# DRV__2024-10-17.net
KiCad netlist of a schematic drawn in EasyEDA Pro
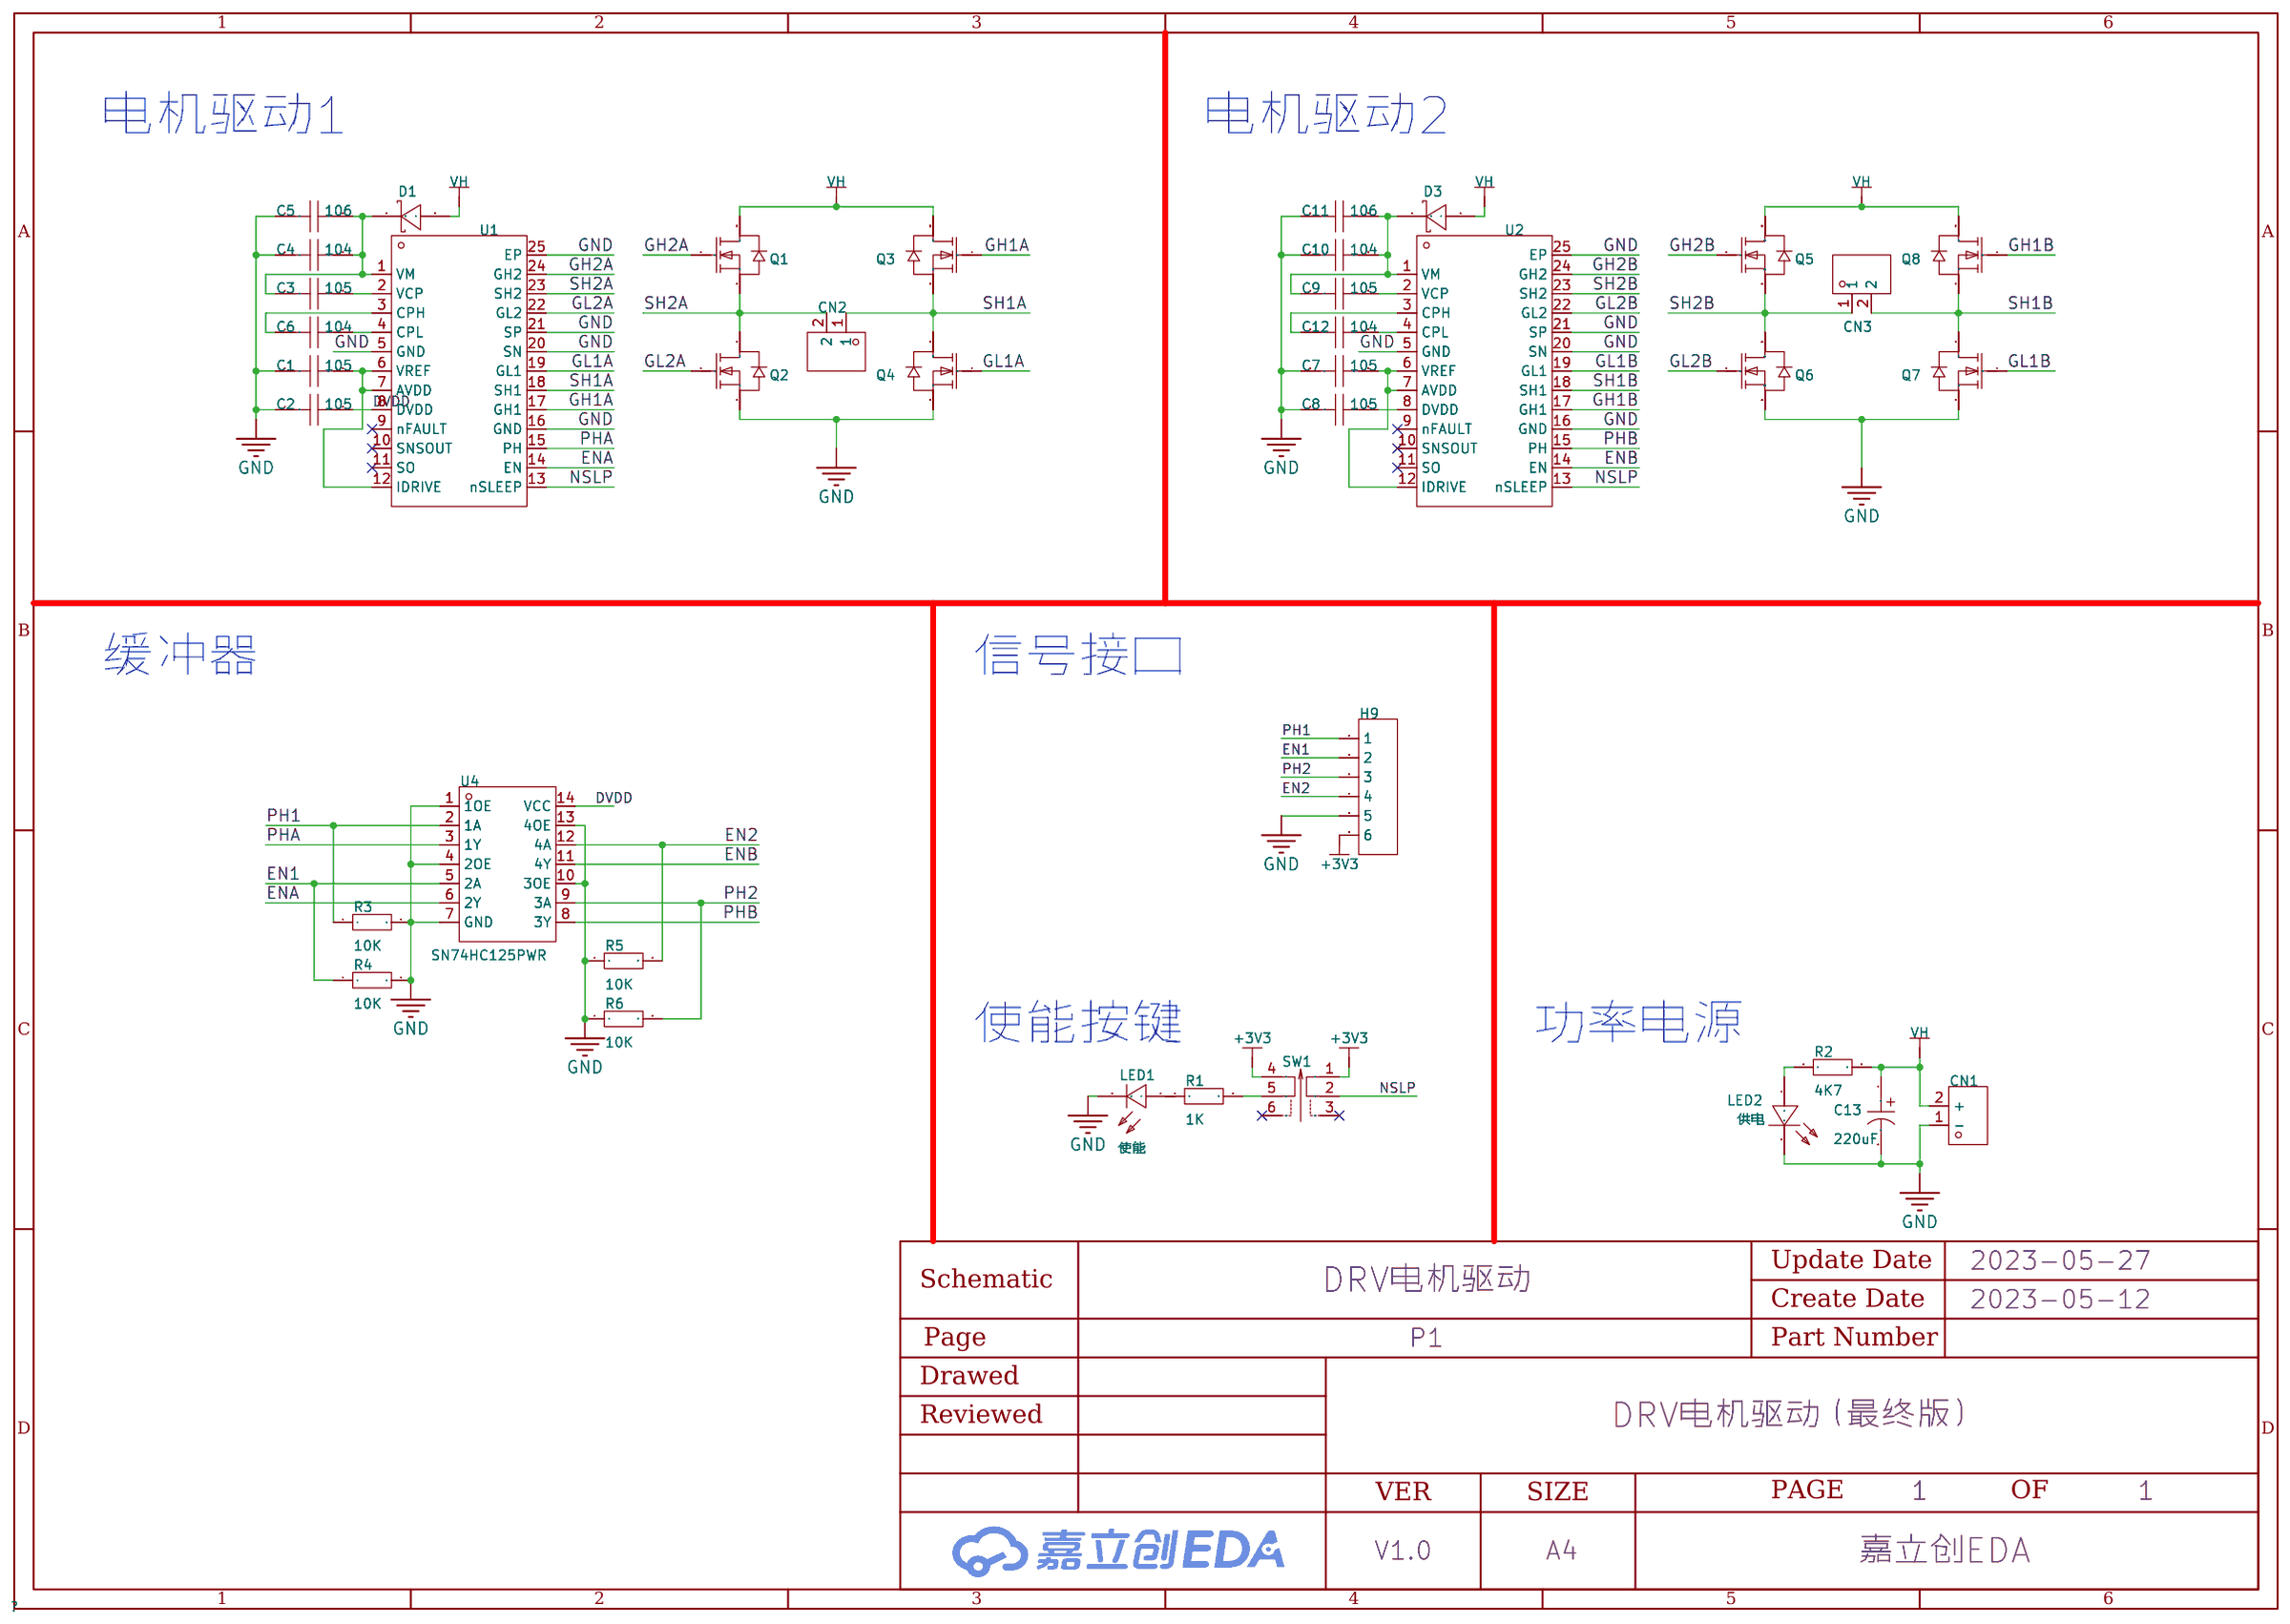
[diagram p0: schematic sheet]

(export (version "E")
  (design (tool "Eeschema 10.0.6"))
  (components
    (comp (ref "C1")
      (value "105")
      (footprint "easyedapro:C0603")
      (description "容值:100nF;精度:±10%;额定电压:50V;温度系数:X7R;")
      (libsource (lib "easyedapro") (part "C1210X7R475K630NT"))
    )
    (comp (ref "C2")
      (value "105")
      (footprint "easyedapro:C0603")
      (description "容值:100nF;精度:±10%;额定电压:50V;温度系数:X7R;")
      (libsource (lib "easyedapro") (part "C1210X7R475K630NT"))
    )
    (comp (ref "C3")
      (value "105")
      (footprint "easyedapro:C0603")
      (description "容值:100nF;精度:±10%;额定电压:50V;温度系数:X7R;")
      (libsource (lib "easyedapro") (part "C1210X7R475K630NT"))
    )
    (comp (ref "C4")
      (value "104")
      (footprint "easyedapro:C0603")
      (description "容值:100nF;精度:±10%;额定电压:50V;温度系数:X7R;")
      (libsource (lib "easyedapro") (part "C1210X7R475K630NT"))
    )
    (comp (ref "C5")
      (value "106")
      (footprint "easyedapro:C0603")
      (description "容值:100nF;精度:±10%;额定电压:50V;温度系数:X7R;")
      (libsource (lib "easyedapro") (part "C1210X7R475K630NT"))
    )
    (comp (ref "C6")
      (value "104")
      (footprint "easyedapro:C0603")
      (description "容值:100nF;精度:±10%;额定电压:50V;温度系数:X7R;")
      (libsource (lib "easyedapro") (part "C1210X7R475K630NT"))
    )
    (comp (ref "C7")
      (value "105")
      (footprint "easyedapro:C0603")
      (description "容值:100nF;精度:±10%;额定电压:50V;温度系数:X7R;")
      (libsource (lib "easyedapro") (part "C1210X7R475K630NT"))
    )
    (comp (ref "C8")
      (value "105")
      (footprint "easyedapro:C0603")
      (description "容值:100nF;精度:±10%;额定电压:50V;温度系数:X7R;")
      (libsource (lib "easyedapro") (part "C1210X7R475K630NT"))
    )
    (comp (ref "C9")
      (value "105")
      (footprint "easyedapro:C0603")
      (description "容值:100nF;精度:±10%;额定电压:50V;温度系数:X7R;")
      (libsource (lib "easyedapro") (part "C1210X7R475K630NT"))
    )
    (comp (ref "C10")
      (value "104")
      (footprint "easyedapro:C0603")
      (description "容值:100nF;精度:±10%;额定电压:50V;温度系数:X7R;")
      (libsource (lib "easyedapro") (part "C1210X7R475K630NT"))
    )
    (comp (ref "C11")
      (value "106")
      (footprint "easyedapro:C0603")
      (description "容值:100nF;精度:±10%;额定电压:50V;温度系数:X7R;")
      (libsource (lib "easyedapro") (part "C1210X7R475K630NT"))
    )
    (comp (ref "C12")
      (value "104")
      (footprint "easyedapro:C0603")
      (description "容值:100nF;精度:±10%;额定电压:50V;温度系数:X7R;")
      (libsource (lib "easyedapro") (part "C1210X7R475K630NT"))
    )
    (comp (ref "C13")
      (value "220uF")
      (footprint "easyedapro:CAP-TH_BD8.0-P3.50-D0.6-FD")
      (description "类型:-;容值:220uF;精度:±20%;额定电压:25V;电容体直径:-;电容体长度:-;脚间距:-;纹波电流:-;等效串联电阻:-;工作寿命:-;工作温度:-;")
      (fields (field (name "Manufacturer Part") "250ARHA221M08A2") (field (name "Manufacturer") "APAQ(钰邦)"))
      (libsource (lib "easyedapro") (part "250ARHA221M08A2"))
    )
    (comp (ref "CN1")
      (value "~")
      (footprint "easyedapro:CONN-TH_XT30UPB-M")
      (fields (field (name "Manufacturer Part") "XT30UPB-M") (field (name "Manufacturer") "AMASS(艾迈斯)"))
      (libsource (lib "easyedapro") (part "XT30UPB-M"))
    )
    (comp (ref "CN2")
      (value "KF301-5.0-2P")
      (footprint "easyedapro:CONN-TH_P5.00_KF301-5.0-2P")
      (description "间距:5mm;排数:1;每排PIN数:2;安装方式:直针;额定电流:17A;额定电压:250V;线规 - AWG:14~22;线规 - mm?:1.5;工作温度范围:-30~+120;颜色:蓝色;")
      (fields (field (name "Manufacturer") "KEFA(科发)"))
      (libsource (lib "easyedapro") (part "KF301-5.0-2P"))
    )
    (comp (ref "CN3")
      (value "KF301-5.0-2P")
      (footprint "easyedapro:CONN-TH_P5.00_KF301-5.0-2P")
      (description "间距:5mm;排数:1;每排PIN数:2;安装方式:直针;额定电流:17A;额定电压:250V;线规 - AWG:14~22;线规 - mm?:1.5;工作温度范围:-30~+120;颜色:蓝色;")
      (fields (field (name "Manufacturer") "KEFA(科发)"))
      (libsource (lib "easyedapro") (part "KF301-5.0-2P"))
    )
    (comp (ref "D1")
      (value "1N5819WS")
      (footprint "easyedapro:SOD-323_L1.8-W1.3-LS2.5-RD")
      (description "直流反向耐压(Vr):40V;平均整流电流(Io):1A;正向压降(Vf):900mV@3A;")
      (fields (field (name "Manufacturer") "PJSEMI(平晶微)"))
      (libsource (lib "easyedapro") (part "1N5819WS_C440261"))
    )
    (comp (ref "D3")
      (value "1N5819WS")
      (footprint "easyedapro:SOD-323_L1.8-W1.3-LS2.5-RD")
      (description "直流反向耐压(Vr):40V;平均整流电流(Io):1A;正向压降(Vf):900mV@3A;")
      (fields (field (name "Manufacturer") "PJSEMI(平晶微)"))
      (libsource (lib "easyedapro") (part "1N5819WS_C440261"))
    )
    (comp (ref "H9")
      (value "~")
      (footprint "easyedapro:HDR-TH_6P-P2.54-V-M-1")
      (libsource (lib "easyedapro") (part "Header-Male-2.54_1x6"))
    )
    (comp (ref "LED1")
      (value "使能")
      (footprint "easyedapro:LED0603-R-RD")
      (description "照明颜色:普绿/黄绿;色温 - CCT（K）:-;主波长/色坐标:569.5~577.5nm;")
      (fields
        (field (name "Manufacturer Part") "19-217/G7C-AN1P2/3T")
        (field (name "Manufacturer") "EVERLIGHT(台湾亿光)")
      )
      (libsource (lib "easyedapro") (part "19-217/G7C-AN1P2/3T"))
    )
    (comp (ref "LED2")
      (value "供电")
      (footprint "easyedapro:LED0603-R-RD")
      (description "发光颜色:红灯;")
      (fields (field (name "Manufacturer Part") "TLMS1000-GS08") (field (name "Manufacturer") "VISHAY(威世)"))
      (libsource (lib "easyedapro") (part "TLMS1000-GS08"))
    )
    (comp (ref "Q1")
      (value "CSD17570Q5B")
      (footprint "easyedapro:PG-TSON-8_L5.0-W6.0-P1.27-BL-EP_BSC021N08NS5")
      (fields (field (name "Manufacturer") "TI(德州仪器)"))
      (libsource (lib "easyedapro") (part "CSD17570Q5B"))
    )
    (comp (ref "Q2")
      (value "CSD17570Q5B")
      (footprint "easyedapro:PG-TSON-8_L5.0-W6.0-P1.27-BL-EP_BSC021N08NS5")
      (fields (field (name "Manufacturer") "TI(德州仪器)"))
      (libsource (lib "easyedapro") (part "CSD17570Q5B"))
    )
    (comp (ref "Q3")
      (value "CSD17570Q5B")
      (footprint "easyedapro:PG-TSON-8_L5.0-W6.0-P1.27-BL-EP_BSC021N08NS5")
      (fields (field (name "Manufacturer") "TI(德州仪器)"))
      (libsource (lib "easyedapro") (part "CSD17570Q5B"))
    )
    (comp (ref "Q4")
      (value "CSD17570Q5B")
      (footprint "easyedapro:PG-TSON-8_L5.0-W6.0-P1.27-BL-EP_BSC021N08NS5")
      (fields (field (name "Manufacturer") "TI(德州仪器)"))
      (libsource (lib "easyedapro") (part "CSD17570Q5B"))
    )
    (comp (ref "Q5")
      (value "CSD17570Q5B")
      (footprint "easyedapro:PG-TSON-8_L5.0-W6.0-P1.27-BL-EP_BSC021N08NS5")
      (fields (field (name "Manufacturer") "TI(德州仪器)"))
      (libsource (lib "easyedapro") (part "CSD17570Q5B"))
    )
    (comp (ref "Q6")
      (value "CSD17570Q5B")
      (footprint "easyedapro:PG-TSON-8_L5.0-W6.0-P1.27-BL-EP_BSC021N08NS5")
      (fields (field (name "Manufacturer") "TI(德州仪器)"))
      (libsource (lib "easyedapro") (part "CSD17570Q5B"))
    )
    (comp (ref "Q7")
      (value "CSD17570Q5B")
      (footprint "easyedapro:PG-TSON-8_L5.0-W6.0-P1.27-BL-EP_BSC021N08NS5")
      (fields (field (name "Manufacturer") "TI(德州仪器)"))
      (libsource (lib "easyedapro") (part "CSD17570Q5B"))
    )
    (comp (ref "Q8")
      (value "CSD17570Q5B")
      (footprint "easyedapro:PG-TSON-8_L5.0-W6.0-P1.27-BL-EP_BSC021N08NS5")
      (fields (field (name "Manufacturer") "TI(德州仪器)"))
      (libsource (lib "easyedapro") (part "CSD17570Q5B"))
    )
    (comp (ref "R1") (value "1K") (footprint "easyedapro:R0603") (libsource (lib "easyedapro") (part "电阻")))
    (comp (ref "R2") (value "4K7") (footprint "easyedapro:R0603") (libsource (lib "easyedapro") (part "电阻")))
    (comp (ref "R3") (value "10K") (footprint "easyedapro:R0603") (libsource (lib "easyedapro") (part "电阻")))
    (comp (ref "R4") (value "10K") (footprint "easyedapro:R0603") (libsource (lib "easyedapro") (part "电阻")))
    (comp (ref "R5") (value "10K") (footprint "easyedapro:R0603") (libsource (lib "easyedapro") (part "电阻")))
    (comp (ref "R6") (value "10K") (footprint "easyedapro:R0603") (libsource (lib "easyedapro") (part "电阻")))
    (comp (ref "SW1")
      (value "使能开关")
      (footprint "easyedapro:SW-TH_6P-L5.8-W5.8-P2.00-LS4.5-BL")
      (fields (field (name "Manufacturer Part") "PB22E60L") (field (name "Manufacturer") "CIKI(皓富)"))
      (libsource (lib "easyedapro") (part "PB22E60L"))
    )
    (comp (ref "U1")
      (value "DRV8701ERGER")
      (footprint "easyedapro:VQFN-24_L4.0-W4.0-P0.50-BL-EP2.8")
      (description "DRV8701 DRV8701 H 桥栅极驱动器")
      (fields (field (name "Manufacturer") "TI(德州仪器)"))
      (libsource (lib "easyedapro") (part "DRV8701ERGER"))
    )
    (comp (ref "U2")
      (value "DRV8701ERGER")
      (footprint "easyedapro:VQFN-24_L4.0-W4.0-P0.50-BL-EP2.8")
      (description "DRV8701 DRV8701 H 桥栅极驱动器")
      (fields (field (name "Manufacturer") "TI(德州仪器)"))
      (libsource (lib "easyedapro") (part "DRV8701ERGER"))
    )
    (comp (ref "U4")
      (value "SN74HC125PWR")
      (footprint "easyedapro:TSSOP-14_L5.0-W4.4-P0.65-LS6.4-TL")
      (description "类型:缓冲器，非反相;电源电压:2V~6V;输入类型:-;输出类型:三态;低电平输出电流(IOL):7.8mA;高电平输出电流(IOH):7.8mA;工作温度:-40°C~+85°C;")
      (fields (field (name "Manufacturer") "TI(德州仪器)"))
      (libsource (lib "easyedapro") (part "SN74HC125PWRG4"))
    )
  )
  (nets
    (net (code "1") (name "+3V3") (class "Default")
      (node (ref "H9") (pin "6") (pinfunction "6_6") (pintype "input"))
      (node (ref "SW1") (pin "1") (pinfunction "1_1") (pintype "input"))
      (node (ref "SW1") (pin "4") (pinfunction "4_4") (pintype "input"))
    )
    (net (code "2") (name "/DVDD") (class "Default")
      (node (ref "C2") (pin "2") (pinfunction "2_2") (pintype "input"))
      (node (ref "U1") (pin "8") (pinfunction "DVDD_8") (pintype "input"))
      (node (ref "U4") (pin "14") (pinfunction "VCC_14") (pintype "input"))
    )
    (net (code "3") (name "/EN1") (class "Default")
      (node (ref "H9") (pin "2") (pinfunction "2_2") (pintype "input"))
      (node (ref "R4") (pin "1") (pinfunction "1_1") (pintype "input"))
      (node (ref "U4") (pin "5") (pinfunction "2A_5") (pintype "input"))
    )
    (net (code "4") (name "/EN2") (class "Default")
      (node (ref "H9") (pin "4") (pinfunction "4_4") (pintype "input"))
      (node (ref "R5") (pin "2") (pinfunction "2_2") (pintype "input"))
      (node (ref "U4") (pin "12") (pinfunction "4A_12") (pintype "input"))
    )
    (net (code "5") (name "/ENA") (class "Default")
      (node (ref "U1") (pin "14") (pinfunction "EN_14") (pintype "input"))
      (node (ref "U4") (pin "6") (pinfunction "2Y_6") (pintype "input"))
    )
    (net (code "6") (name "/ENB") (class "Default")
      (node (ref "U2") (pin "14") (pinfunction "EN_14") (pintype "input"))
      (node (ref "U4") (pin "11") (pinfunction "4Y_11") (pintype "input"))
    )
    (net (code "7") (name "/GH1A") (class "Default")
      (node (ref "Q3") (pin "4") (pinfunction "G_4") (pintype "input"))
      (node (ref "U1") (pin "17") (pinfunction "GH1_17") (pintype "input"))
    )
    (net (code "8") (name "/GH1B") (class "Default")
      (node (ref "Q8") (pin "4") (pinfunction "G_4") (pintype "input"))
      (node (ref "U2") (pin "17") (pinfunction "GH1_17") (pintype "input"))
    )
    (net (code "9") (name "/GH2A") (class "Default")
      (node (ref "Q1") (pin "4") (pinfunction "G_4") (pintype "input"))
      (node (ref "U1") (pin "24") (pinfunction "GH2_24") (pintype "input"))
    )
    (net (code "10") (name "/GH2B") (class "Default")
      (node (ref "Q5") (pin "4") (pinfunction "G_4") (pintype "input"))
      (node (ref "U2") (pin "24") (pinfunction "GH2_24") (pintype "input"))
    )
    (net (code "11") (name "/GL1A") (class "Default")
      (node (ref "Q4") (pin "4") (pinfunction "G_4") (pintype "input"))
      (node (ref "U1") (pin "19") (pinfunction "GL1_19") (pintype "input"))
    )
    (net (code "12") (name "/GL1B") (class "Default")
      (node (ref "Q7") (pin "4") (pinfunction "G_4") (pintype "input"))
      (node (ref "U2") (pin "19") (pinfunction "GL1_19") (pintype "input"))
    )
    (net (code "13") (name "/GL2A") (class "Default")
      (node (ref "Q2") (pin "4") (pinfunction "G_4") (pintype "input"))
      (node (ref "U1") (pin "22") (pinfunction "GL2_22") (pintype "input"))
    )
    (net (code "14") (name "/GL2B") (class "Default")
      (node (ref "Q6") (pin "4") (pinfunction "G_4") (pintype "input"))
      (node (ref "U2") (pin "22") (pinfunction "GL2_22") (pintype "input"))
    )
    (net (code "15") (name "/NSLP") (class "Default")
      (node (ref "SW1") (pin "2") (pinfunction "2_2") (pintype "input"))
      (node (ref "U1") (pin "13") (pinfunction "nSLEEP_13") (pintype "input"))
      (node (ref "U2") (pin "13") (pinfunction "nSLEEP_13") (pintype "input"))
    )
    (net (code "16") (name "/PH1") (class "Default")
      (node (ref "H9") (pin "1") (pinfunction "1_1") (pintype "input"))
      (node (ref "R3") (pin "1") (pinfunction "1_1") (pintype "input"))
      (node (ref "U4") (pin "2") (pinfunction "1A_2") (pintype "input"))
    )
    (net (code "17") (name "/PH2") (class "Default")
      (node (ref "H9") (pin "3") (pinfunction "3_3") (pintype "input"))
      (node (ref "R6") (pin "2") (pinfunction "2_2") (pintype "input"))
      (node (ref "U4") (pin "9") (pinfunction "3A_9") (pintype "input"))
    )
    (net (code "18") (name "/PHA") (class "Default")
      (node (ref "U1") (pin "15") (pinfunction "PH_15") (pintype "input"))
      (node (ref "U4") (pin "3") (pinfunction "1Y_3") (pintype "input"))
    )
    (net (code "19") (name "/PHB") (class "Default")
      (node (ref "U2") (pin "15") (pinfunction "PH_15") (pintype "input"))
      (node (ref "U4") (pin "8") (pinfunction "3Y_8") (pintype "input"))
    )
    (net (code "20") (name "/SH1A") (class "Default")
      (node (ref "CN2") (pin "1") (pinfunction "1_1") (pintype "input"))
      (node (ref "Q3") (pin "1") (pinfunction "S_1") (pintype "input"))
      (node (ref "Q3") (pin "2") (pinfunction "S_2") (pintype "input"))
      (node (ref "Q3") (pin "3") (pinfunction "S_3") (pintype "input"))
      (node (ref "Q4") (pin "5") (pinfunction "D_5") (pintype "input"))
      (node (ref "Q4") (pin "6") (pinfunction "D_6") (pintype "input"))
      (node (ref "Q4") (pin "7") (pinfunction "D_7") (pintype "input"))
      (node (ref "Q4") (pin "8") (pinfunction "D_8") (pintype "input"))
      (node (ref "U1") (pin "18") (pinfunction "SH1_18") (pintype "input"))
    )
    (net (code "21") (name "/SH1B") (class "Default")
      (node (ref "CN3") (pin "2") (pinfunction "2_2") (pintype "input"))
      (node (ref "Q7") (pin "5") (pinfunction "D_5") (pintype "input"))
      (node (ref "Q7") (pin "6") (pinfunction "D_6") (pintype "input"))
      (node (ref "Q7") (pin "7") (pinfunction "D_7") (pintype "input"))
      (node (ref "Q7") (pin "8") (pinfunction "D_8") (pintype "input"))
      (node (ref "Q8") (pin "1") (pinfunction "S_1") (pintype "input"))
      (node (ref "Q8") (pin "2") (pinfunction "S_2") (pintype "input"))
      (node (ref "Q8") (pin "3") (pinfunction "S_3") (pintype "input"))
      (node (ref "U2") (pin "18") (pinfunction "SH1_18") (pintype "input"))
    )
    (net (code "22") (name "/SH2A") (class "Default")
      (node (ref "CN2") (pin "2") (pinfunction "2_2") (pintype "input"))
      (node (ref "Q1") (pin "1") (pinfunction "S_1") (pintype "input"))
      (node (ref "Q1") (pin "2") (pinfunction "S_2") (pintype "input"))
      (node (ref "Q1") (pin "3") (pinfunction "S_3") (pintype "input"))
      (node (ref "Q2") (pin "5") (pinfunction "D_5") (pintype "input"))
      (node (ref "Q2") (pin "6") (pinfunction "D_6") (pintype "input"))
      (node (ref "Q2") (pin "7") (pinfunction "D_7") (pintype "input"))
      (node (ref "Q2") (pin "8") (pinfunction "D_8") (pintype "input"))
      (node (ref "U1") (pin "23") (pinfunction "SH2_23") (pintype "input"))
    )
    (net (code "23") (name "/SH2B") (class "Default")
      (node (ref "CN3") (pin "1") (pinfunction "1_1") (pintype "input"))
      (node (ref "Q5") (pin "1") (pinfunction "S_1") (pintype "input"))
      (node (ref "Q5") (pin "2") (pinfunction "S_2") (pintype "input"))
      (node (ref "Q5") (pin "3") (pinfunction "S_3") (pintype "input"))
      (node (ref "Q6") (pin "5") (pinfunction "D_5") (pintype "input"))
      (node (ref "Q6") (pin "6") (pinfunction "D_6") (pintype "input"))
      (node (ref "Q6") (pin "7") (pinfunction "D_7") (pintype "input"))
      (node (ref "Q6") (pin "8") (pinfunction "D_8") (pintype "input"))
      (node (ref "U2") (pin "23") (pinfunction "SH2_23") (pintype "input"))
    )
    (net (code "24") (name "GND") (class "Default")
      (node (ref "C1") (pin "1") (pinfunction "1_1") (pintype "input"))
      (node (ref "C10") (pin "1") (pinfunction "1_1") (pintype "input"))
      (node (ref "C11") (pin "1") (pinfunction "1_1") (pintype "input"))
      (node (ref "C13") (pin "2") (pinfunction "2_2") (pintype "input"))
      (node (ref "C2") (pin "1") (pinfunction "1_1") (pintype "input"))
      (node (ref "C4") (pin "1") (pinfunction "1_1") (pintype "input"))
      (node (ref "C5") (pin "1") (pinfunction "1_1") (pintype "input"))
      (node (ref "C7") (pin "1") (pinfunction "1_1") (pintype "input"))
      (node (ref "C8") (pin "1") (pinfunction "1_1") (pintype "input"))
      (node (ref "CN1") (pin "1") (pinfunction "-_1") (pintype "input"))
      (node (ref "H9") (pin "5") (pinfunction "5_5") (pintype "input"))
      (node (ref "LED1") (pin "2") (pinfunction "C_2") (pintype "input"))
      (node (ref "LED2") (pin "2") (pinfunction "K_2") (pintype "input"))
      (node (ref "Q2") (pin "1") (pinfunction "S_1") (pintype "input"))
      (node (ref "Q2") (pin "2") (pinfunction "S_2") (pintype "input"))
      (node (ref "Q2") (pin "3") (pinfunction "S_3") (pintype "input"))
      (node (ref "Q4") (pin "1") (pinfunction "S_1") (pintype "input"))
      (node (ref "Q4") (pin "2") (pinfunction "S_2") (pintype "input"))
      (node (ref "Q4") (pin "3") (pinfunction "S_3") (pintype "input"))
      (node (ref "Q6") (pin "1") (pinfunction "S_1") (pintype "input"))
      (node (ref "Q6") (pin "2") (pinfunction "S_2") (pintype "input"))
      (node (ref "Q6") (pin "3") (pinfunction "S_3") (pintype "input"))
      (node (ref "Q7") (pin "1") (pinfunction "S_1") (pintype "input"))
      (node (ref "Q7") (pin "2") (pinfunction "S_2") (pintype "input"))
      (node (ref "Q7") (pin "3") (pinfunction "S_3") (pintype "input"))
      (node (ref "R3") (pin "2") (pinfunction "2_2") (pintype "input"))
      (node (ref "R4") (pin "2") (pinfunction "2_2") (pintype "input"))
      (node (ref "R5") (pin "1") (pinfunction "1_1") (pintype "input"))
      (node (ref "R6") (pin "1") (pinfunction "1_1") (pintype "input"))
      (node (ref "U1") (pin "16") (pinfunction "GND_16") (pintype "input"))
      (node (ref "U1") (pin "20") (pinfunction "SN_20") (pintype "input"))
      (node (ref "U1") (pin "21") (pinfunction "SP_21") (pintype "input"))
      (node (ref "U1") (pin "25") (pinfunction "EP_25") (pintype "input"))
      (node (ref "U1") (pin "5") (pinfunction "GND_5") (pintype "input"))
      (node (ref "U2") (pin "16") (pinfunction "GND_16") (pintype "input"))
      (node (ref "U2") (pin "20") (pinfunction "SN_20") (pintype "input"))
      (node (ref "U2") (pin "21") (pinfunction "SP_21") (pintype "input"))
      (node (ref "U2") (pin "25") (pinfunction "EP_25") (pintype "input"))
      (node (ref "U2") (pin "5") (pinfunction "GND_5") (pintype "input"))
      (node (ref "U4") (pin "1") (pinfunction "1OE_1") (pintype "input"))
      (node (ref "U4") (pin "10") (pinfunction "3OE_10") (pintype "input"))
      (node (ref "U4") (pin "13") (pinfunction "4OE_13") (pintype "input"))
      (node (ref "U4") (pin "4") (pinfunction "2OE_4") (pintype "input"))
      (node (ref "U4") (pin "7") (pinfunction "GND_7") (pintype "input"))
    )
    (net (code "25") (name "Net-(D1-C)") (class "Default")
      (node (ref "C3") (pin "1") (pinfunction "1_1") (pintype "input"))
      (node (ref "C4") (pin "2") (pinfunction "2_2") (pintype "input"))
      (node (ref "C5") (pin "2") (pinfunction "2_2") (pintype "input"))
      (node (ref "D1") (pin "1") (pinfunction "C_1") (pintype "input"))
      (node (ref "U1") (pin "1") (pinfunction "VM_1") (pintype "input"))
    )
    (net (code "26") (name "Net-(D3-C)") (class "Default")
      (node (ref "C10") (pin "2") (pinfunction "2_2") (pintype "input"))
      (node (ref "C11") (pin "2") (pinfunction "2_2") (pintype "input"))
      (node (ref "C9") (pin "1") (pinfunction "1_1") (pintype "input"))
      (node (ref "D3") (pin "1") (pinfunction "C_1") (pintype "input"))
      (node (ref "U2") (pin "1") (pinfunction "VM_1") (pintype "input"))
    )
    (net (code "27") (name "Net-(LED1-A)") (class "Default")
      (node (ref "LED1") (pin "1") (pinfunction "A_1") (pintype "input"))
      (node (ref "R1") (pin "1") (pinfunction "1_1") (pintype "input"))
    )
    (net (code "28") (name "Net-(LED2-A)") (class "Default")
      (node (ref "LED2") (pin "1") (pinfunction "A_1") (pintype "input"))
      (node (ref "R2") (pin "1") (pinfunction "1_1") (pintype "input"))
    )
    (net (code "29") (name "Net-(R1-Pad2)") (class "Default")
      (node (ref "R1") (pin "2") (pinfunction "2_2") (pintype "input"))
      (node (ref "SW1") (pin "5") (pinfunction "5_5") (pintype "input"))
    )
    (net (code "30") (name "Net-(U1-AVDD)") (class "Default")
      (node (ref "C1") (pin "2") (pinfunction "2_2") (pintype "input"))
      (node (ref "U1") (pin "12") (pinfunction "IDRIVE_12") (pintype "input"))
      (node (ref "U1") (pin "6") (pinfunction "VREF_6") (pintype "input"))
      (node (ref "U1") (pin "7") (pinfunction "AVDD_7") (pintype "input"))
    )
    (net (code "31") (name "Net-(U1-CPH)") (class "Default")
      (node (ref "C6") (pin "1") (pinfunction "1_1") (pintype "input"))
      (node (ref "U1") (pin "3") (pinfunction "CPH_3") (pintype "input"))
    )
    (net (code "32") (name "Net-(U1-CPL)") (class "Default")
      (node (ref "C6") (pin "2") (pinfunction "2_2") (pintype "input"))
      (node (ref "U1") (pin "4") (pinfunction "CPL_4") (pintype "input"))
    )
    (net (code "33") (name "Net-(U1-VCP)") (class "Default")
      (node (ref "C3") (pin "2") (pinfunction "2_2") (pintype "input"))
      (node (ref "U1") (pin "2") (pinfunction "VCP_2") (pintype "input"))
    )
    (net (code "34") (name "Net-(U2-AVDD)") (class "Default")
      (node (ref "C7") (pin "2") (pinfunction "2_2") (pintype "input"))
      (node (ref "U2") (pin "12") (pinfunction "IDRIVE_12") (pintype "input"))
      (node (ref "U2") (pin "6") (pinfunction "VREF_6") (pintype "input"))
      (node (ref "U2") (pin "7") (pinfunction "AVDD_7") (pintype "input"))
    )
    (net (code "35") (name "Net-(U2-CPH)") (class "Default")
      (node (ref "C12") (pin "1") (pinfunction "1_1") (pintype "input"))
      (node (ref "U2") (pin "3") (pinfunction "CPH_3") (pintype "input"))
    )
    (net (code "36") (name "Net-(U2-CPL)") (class "Default")
      (node (ref "C12") (pin "2") (pinfunction "2_2") (pintype "input"))
      (node (ref "U2") (pin "4") (pinfunction "CPL_4") (pintype "input"))
    )
    (net (code "37") (name "Net-(U2-DVDD)") (class "Default")
      (node (ref "C8") (pin "2") (pinfunction "2_2") (pintype "input"))
      (node (ref "U2") (pin "8") (pinfunction "DVDD_8") (pintype "input"))
    )
    (net (code "38") (name "Net-(U2-VCP)") (class "Default")
      (node (ref "C9") (pin "2") (pinfunction "2_2") (pintype "input"))
      (node (ref "U2") (pin "2") (pinfunction "VCP_2") (pintype "input"))
    )
    (net (code "39") (name "VH") (class "Default")
      (node (ref "C13") (pin "1") (pinfunction "1_1") (pintype "input"))
      (node (ref "CN1") (pin "2") (pinfunction "+_2") (pintype "input"))
      (node (ref "D1") (pin "2") (pinfunction "A_2") (pintype "input"))
      (node (ref "D3") (pin "2") (pinfunction "A_2") (pintype "input"))
      (node (ref "Q1") (pin "5") (pinfunction "D_5") (pintype "input"))
      (node (ref "Q1") (pin "6") (pinfunction "D_6") (pintype "input"))
      (node (ref "Q1") (pin "7") (pinfunction "D_7") (pintype "input"))
      (node (ref "Q1") (pin "8") (pinfunction "D_8") (pintype "input"))
      (node (ref "Q3") (pin "5") (pinfunction "D_5") (pintype "input"))
      (node (ref "Q3") (pin "6") (pinfunction "D_6") (pintype "input"))
      (node (ref "Q3") (pin "7") (pinfunction "D_7") (pintype "input"))
      (node (ref "Q3") (pin "8") (pinfunction "D_8") (pintype "input"))
      (node (ref "Q5") (pin "5") (pinfunction "D_5") (pintype "input"))
      (node (ref "Q5") (pin "6") (pinfunction "D_6") (pintype "input"))
      (node (ref "Q5") (pin "7") (pinfunction "D_7") (pintype "input"))
      (node (ref "Q5") (pin "8") (pinfunction "D_8") (pintype "input"))
      (node (ref "Q8") (pin "5") (pinfunction "D_5") (pintype "input"))
      (node (ref "Q8") (pin "6") (pinfunction "D_6") (pintype "input"))
      (node (ref "Q8") (pin "7") (pinfunction "D_7") (pintype "input"))
      (node (ref "Q8") (pin "8") (pinfunction "D_8") (pintype "input"))
      (node (ref "R2") (pin "2") (pinfunction "2_2") (pintype "input"))
    )
    (net (code "40") (name "unconnected-(SW1-Pad3)") (class "Default")
      (node (ref "SW1") (pin "3") (pinfunction "3_3") (pintype "input+no_connect"))
    )
    (net (code "41") (name "unconnected-(SW1-Pad6)") (class "Default")
      (node (ref "SW1") (pin "6") (pinfunction "6_6") (pintype "input+no_connect"))
    )
    (net (code "42") (name "unconnected-(U1-SNSOUT-Pad10)") (class "Default")
      (node (ref "U1") (pin "10") (pinfunction "SNSOUT_10") (pintype "input+no_connect"))
    )
    (net (code "43") (name "unconnected-(U1-SO-Pad11)") (class "Default")
      (node (ref "U1") (pin "11") (pinfunction "SO_11") (pintype "input+no_connect"))
    )
    (net (code "44") (name "unconnected-(U1-nFAULT-Pad9)") (class "Default")
      (node (ref "U1") (pin "9") (pinfunction "nFAULT_9") (pintype "input+no_connect"))
    )
    (net (code "45") (name "unconnected-(U2-SNSOUT-Pad10)") (class "Default")
      (node (ref "U2") (pin "10") (pinfunction "SNSOUT_10") (pintype "input+no_connect"))
    )
    (net (code "46") (name "unconnected-(U2-SO-Pad11)") (class "Default")
      (node (ref "U2") (pin "11") (pinfunction "SO_11") (pintype "input+no_connect"))
    )
    (net (code "47") (name "unconnected-(U2-nFAULT-Pad9)") (class "Default")
      (node (ref "U2") (pin "9") (pinfunction "nFAULT_9") (pintype "input+no_connect"))
    )
  )
)
